# Shematic.net
KiCad netlist of a schematic drawn in Altium Designer
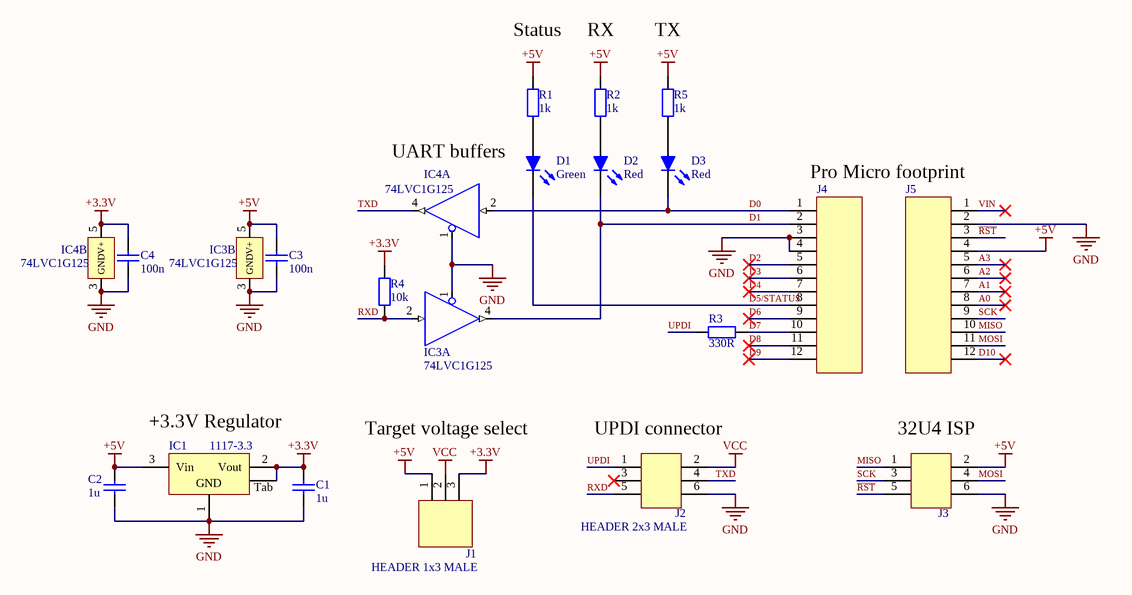
[diagram p0: Shematic.SchDoc]

(export (version "E")
  (design (tool "Eeschema 10.0.6"))
  (components
    (comp (ref "C1")
      (value "1u")
      (footprint "MCUdude_library:0805 CAPACITOR")
      (description "Cap Ceramic 0805 1u 16V Y5V")
      (fields (field (name "Comment") "Generic bipolar capacitor"))
      (libsource (lib "MCUdude_library") (part "CAP-CER-0805-1U-16V"))
    )
    (comp (ref "C2")
      (value "1u")
      (footprint "MCUdude_library:0805 CAPACITOR")
      (description "Cap Ceramic 0805 1u 16V Y5V")
      (fields (field (name "Comment") "Generic bipolar capacitor"))
      (libsource (lib "MCUdude_library") (part "CAP-CER-0805-1U-16V"))
    )
    (comp (ref "C3")
      (value "100n")
      (footprint "MCUdude_library:0805 CAPACITOR")
      (description "Cap Ceramic 0805 100n 50V X7R")
      (fields (field (name "Comment") "Generic bipolar capacitor"))
      (libsource (lib "MCUdude_library") (part "CAP-CER-0805-100N-50V"))
    )
    (comp (ref "C4")
      (value "100n")
      (footprint "MCUdude_library:0805 CAPACITOR")
      (description "Cap Ceramic 0805 100n 50V X7R")
      (fields (field (name "Comment") "Generic bipolar capacitor"))
      (libsource (lib "MCUdude_library") (part "CAP-CER-0805-100N-50V"))
    )
    (comp (ref "D1")
      (value "Green")
      (footprint "MCUdude_library:LED-GREEN-0805")
      (description "LED 0805 Green")
      (libsource (lib "MCUdude_library") (part "LED-0805-GREEN"))
    )
    (comp (ref "D2")
      (value "Red")
      (footprint "MCUdude_library:LED-RED-0805")
      (description "LED 0805 Red")
      (libsource (lib "MCUdude_library") (part "LED-0805-RED"))
    )
    (comp (ref "D3")
      (value "Red")
      (footprint "MCUdude_library:LED-RED-0805")
      (description "LED 0805 Red")
      (libsource (lib "MCUdude_library") (part "LED-0805-RED"))
    )
    (comp (ref "IC1")
      (value "1117-3.3")
      (footprint "MCUdude_library:SOT-223")
      (description "Positive 3.3V regulator 1A SOT-223")
      (libsource (lib "MCUdude_library") (part "REG-POS-3.3V-1117"))
    )
    (comp (ref "IC3")
      (value "74LVC1G125")
      (footprint "MCUdude_library:SOT-353")
      (description "Singe Buffer with 3-State Output")
      (libsource (lib "") (part "IC-74LVC1G125_1"))
    )
    (comp (ref "IC4")
      (value "74LVC1G125")
      (footprint "MCUdude_library:SOT-353")
      (description "Singe Buffer with 3-State Output")
      (libsource (lib "MCUdude_library") (part "IC-74LVC1G125"))
    )
    (comp (ref "J1")
      (value "HEADER 1x3 MALE")
      (footprint "HEADER-MALE-STRAIGHT-1x3-LOCKED")
      (description "Header male straight 1x3")
      (libsource (lib "MCUdude_library") (part "CON-HEADER-MALE-STRAIGHT-1x3"))
    )
    (comp (ref "J2")
      (value "HEADER 2x3 MALE")
      (footprint "HEADER-MALE-STRAIGHT-2x3-LOCKED")
      (description "Header male straight 2x3")
      (libsource (lib "MCUdude_library") (part "CON-HEADER-MALE-STRAIGHT-2x3"))
    )
    (comp (ref "J3")
      (value "HEADER 2x3 MALE")
      (footprint "HEADER-MALE-STRAIGHT-2x3-LOCKED")
      (description "Header male straight 2x3")
      (libsource (lib "MCUdude_library") (part "CON-HEADER-MALE-STRAIGHT-2x3"))
    )
    (comp (ref "J4")
      (value "HEADER 1x12 FEMALE")
      (footprint "HEADER-FEMALE-STRAIGHT-1x12")
      (description "Header female straight 1x12")
      (libsource (lib "") (part "CON-HEADER-FEMALE-STRAIGHT-1x12_1"))
    )
    (comp (ref "J5")
      (value "HEADER 1x12 FEMALE")
      (footprint "HEADER-FEMALE-STRAIGHT-1x12")
      (description "Header female straight 1x12")
      (libsource (lib "MCUdude_library") (part "CON-HEADER-FEMALE-STRAIGHT-1x12"))
    )
    (comp (ref "R1")
      (value "1k")
      (footprint "MCUdude_library:0805 RESISTOR")
      (description "Resistor 0805 1k 1%")
      (fields (field (name "Comment") "Generic resistor"))
      (libsource (lib "MCUdude_library") (part "RES-0805-1k"))
    )
    (comp (ref "R2")
      (value "1k")
      (footprint "MCUdude_library:0805 RESISTOR")
      (description "Resistor 0805 1k 1%")
      (fields (field (name "Comment") "Generic resistor"))
      (libsource (lib "MCUdude_library") (part "RES-0805-1k"))
    )
    (comp (ref "R3")
      (value "330R")
      (footprint "MCUdude_library:0805 RESISTOR")
      (description "Resistor 0805 330R 1%")
      (fields (field (name "Comment") "Generic resistor"))
      (libsource (lib "MCUdude_library") (part "RES-0805-330R"))
    )
    (comp (ref "R4")
      (value "10k")
      (footprint "MCUdude_library:0805 RESISTOR")
      (description "Resistor 0805 10k 1%")
      (fields (field (name "Comment") "Generic resistor"))
      (libsource (lib "MCUdude_library") (part "RES-0805-10k"))
    )
    (comp (ref "R5")
      (value "1k")
      (footprint "MCUdude_library:0805 RESISTOR")
      (description "Resistor 0805 1k 1%")
      (fields (field (name "Comment") "Generic resistor"))
      (libsource (lib "MCUdude_library") (part "RES-0805-1k"))
    )
  )
  (nets
    (net (code "1") (name "+3.3V") (class "Default")
      (node (ref "C1") (pin "2") (pinfunction "2_2") (pintype "passive"))
      (node (ref "C4") (pin "2") (pinfunction "2_2") (pintype "passive"))
      (node (ref "IC1") (pin "2") (pinfunction "Vout_2") (pintype "passive"))
      (node (ref "IC1") (pin "4") (pinfunction "4_4") (pintype "power_in"))
      (node (ref "IC4") (pin "5") (pinfunction "V+_5") (pintype "power_in"))
      (node (ref "J1") (pin "3") (pintype "passive"))
      (node (ref "R4") (pin "2") (pinfunction "2_2") (pintype "passive"))
    )
    (net (code "2") (name "+5V") (class "Default")
      (node (ref "C2") (pin "2") (pinfunction "2_2") (pintype "passive"))
      (node (ref "C3") (pin "2") (pinfunction "2_2") (pintype "passive"))
      (node (ref "IC1") (pin "3") (pinfunction "Vin_3") (pintype "passive"))
      (node (ref "IC3") (pin "5") (pinfunction "V+_5") (pintype "power_in"))
      (node (ref "J1") (pin "1") (pintype "passive"))
      (node (ref "J3") (pin "2") (pintype "passive"))
      (node (ref "J5") (pin "4") (pintype "passive"))
      (node (ref "R1") (pin "1") (pinfunction "1_1") (pintype "passive"))
      (node (ref "R2") (pin "1") (pinfunction "1_1") (pintype "passive"))
      (node (ref "R5") (pin "1") (pinfunction "1_1") (pintype "passive"))
    )
    (net (code "3") (name "/A0") (class "Default")
      (node (ref "J5") (pin "8") (pinfunction "8_8") (pintype "passive+no_connect"))
    )
    (net (code "4") (name "/A1") (class "Default")
      (node (ref "J5") (pin "7") (pinfunction "7_7") (pintype "passive+no_connect"))
    )
    (net (code "5") (name "/A2") (class "Default") (node (ref "J5") (pin "6") (pintype "passive+no_connect")))
    (net (code "6") (name "/A3") (class "Default") (node (ref "J5") (pin "5") (pintype "passive+no_connect")))
    (net (code "7") (name "/D0") (class "Default")
      (node (ref "D3") (pin "K") (pinfunction "K_K") (pintype "passive"))
      (node (ref "IC4") (pin "2") (pinfunction "IN-_2") (pintype "input"))
      (node (ref "J4") (pin "1") (pintype "passive"))
    )
    (net (code "8") (name "/D1") (class "Default")
      (node (ref "D2") (pin "K") (pinfunction "K_K") (pintype "passive"))
      (node (ref "IC3") (pin "4") (pinfunction "OUT_4") (pintype "output"))
      (node (ref "J4") (pin "2") (pintype "passive"))
    )
    (net (code "9") (name "/D2") (class "Default") (node (ref "J4") (pin "5") (pintype "passive+no_connect")))
    (net (code "10") (name "/D3") (class "Default")
      (node (ref "J4") (pin "6") (pintype "passive+no_connect"))
    )
    (net (code "11") (name "/D4") (class "Default")
      (node (ref "J4") (pin "7") (pinfunction "7_7") (pintype "passive+no_connect"))
    )
    (net (code "12") (name "/D5{slash}STATUS") (class "Default")
      (node (ref "D1") (pin "K") (pinfunction "K_K") (pintype "passive"))
      (node (ref "J4") (pin "8") (pinfunction "8_8") (pintype "passive"))
    )
    (net (code "13") (name "/D6") (class "Default")
      (node (ref "J4") (pin "9") (pinfunction "9_9") (pintype "passive+no_connect"))
    )
    (net (code "14") (name "/D7") (class "Default")
      (node (ref "J4") (pin "10") (pinfunction "10_10") (pintype "passive"))
      (node (ref "R3") (pin "1") (pinfunction "1_1") (pintype "passive"))
    )
    (net (code "15") (name "/D8") (class "Default")
      (node (ref "J4") (pin "11") (pinfunction "11_11") (pintype "passive+no_connect"))
    )
    (net (code "16") (name "/D9") (class "Default")
      (node (ref "J4") (pin "12") (pinfunction "12_12") (pintype "passive+no_connect"))
    )
    (net (code "17") (name "/D10") (class "Default")
      (node (ref "J5") (pin "12") (pinfunction "12_12") (pintype "passive+no_connect"))
    )
    (net (code "18") (name "/MISO") (class "Default")
      (node (ref "J3") (pin "1") (pintype "passive"))
      (node (ref "J5") (pin "10") (pinfunction "10_10") (pintype "passive"))
    )
    (net (code "19") (name "/MOSI") (class "Default")
      (node (ref "J3") (pin "4") (pintype "passive"))
      (node (ref "J5") (pin "11") (pinfunction "11_11") (pintype "passive"))
    )
    (net (code "20") (name "/RXD") (class "Default")
      (node (ref "IC3") (pin "2") (pinfunction "IN-_2") (pintype "input"))
      (node (ref "J2") (pin "5") (pintype "passive"))
      (node (ref "R4") (pin "1") (pinfunction "1_1") (pintype "passive"))
    )
    (net (code "21") (name "/SCK") (class "Default")
      (node (ref "J3") (pin "3") (pintype "passive"))
      (node (ref "J5") (pin "9") (pinfunction "9_9") (pintype "passive"))
    )
    (net (code "22") (name "/TXD") (class "Default")
      (node (ref "IC4") (pin "4") (pinfunction "OUT_4") (pintype "output"))
      (node (ref "J2") (pin "4") (pintype "passive"))
    )
    (net (code "23") (name "/UPDI") (class "Default")
      (node (ref "J2") (pin "1") (pintype "passive"))
      (node (ref "R3") (pin "2") (pinfunction "2_2") (pintype "passive"))
    )
    (net (code "24") (name "/VIN") (class "Default")
      (node (ref "J5") (pin "1") (pintype "passive+no_connect"))
    )
    (net (code "25") (name "/~{RST}") (class "Default")
      (node (ref "J3") (pin "5") (pintype "passive"))
      (node (ref "J5") (pin "3") (pintype "passive"))
    )
    (net (code "26") (name "GND") (class "Default")
      (node (ref "C1") (pin "1") (pinfunction "1_1") (pintype "passive"))
      (node (ref "C2") (pin "1") (pinfunction "1_1") (pintype "passive"))
      (node (ref "C3") (pin "1") (pinfunction "1_1") (pintype "passive"))
      (node (ref "C4") (pin "1") (pinfunction "1_1") (pintype "passive"))
      (node (ref "IC1") (pin "1") (pinfunction "GND_1") (pintype "passive"))
      (node (ref "IC3") (pin "1") (pinfunction "~{OE}_1") (pintype "passive"))
      (node (ref "IC3") (pin "3") (pinfunction "GND_3") (pintype "power_in"))
      (node (ref "IC4") (pin "1") (pinfunction "~{OE}_1") (pintype "passive"))
      (node (ref "IC4") (pin "3") (pinfunction "GND_3") (pintype "power_in"))
      (node (ref "J2") (pin "6") (pintype "passive"))
      (node (ref "J3") (pin "6") (pintype "passive"))
      (node (ref "J4") (pin "3") (pintype "passive"))
      (node (ref "J4") (pin "4") (pintype "passive"))
      (node (ref "J5") (pin "2") (pintype "passive"))
    )
    (net (code "27") (name "Net-(D1-PadA)") (class "Default")
      (node (ref "D1") (pin "A") (pinfunction "A_A") (pintype "passive"))
      (node (ref "R1") (pin "2") (pinfunction "2_2") (pintype "passive"))
    )
    (net (code "28") (name "Net-(D2-PadA)") (class "Default")
      (node (ref "D2") (pin "A") (pinfunction "A_A") (pintype "passive"))
      (node (ref "R2") (pin "2") (pinfunction "2_2") (pintype "passive"))
    )
    (net (code "29") (name "Net-(D3-PadA)") (class "Default")
      (node (ref "D3") (pin "A") (pinfunction "A_A") (pintype "passive"))
      (node (ref "R5") (pin "2") (pinfunction "2_2") (pintype "passive"))
    )
    (net (code "30") (name "VCC") (class "Default")
      (node (ref "J1") (pin "2") (pintype "passive"))
      (node (ref "J2") (pin "2") (pintype "passive"))
    )
    (net (code "31") (name "unconnected-(J2-Pad3)") (class "Default")
      (node (ref "J2") (pin "3") (pintype "passive+no_connect"))
    )
  )
)
